# rpi_gnss_board.net
KiCad netlist of a schematic drawn in EAGLE
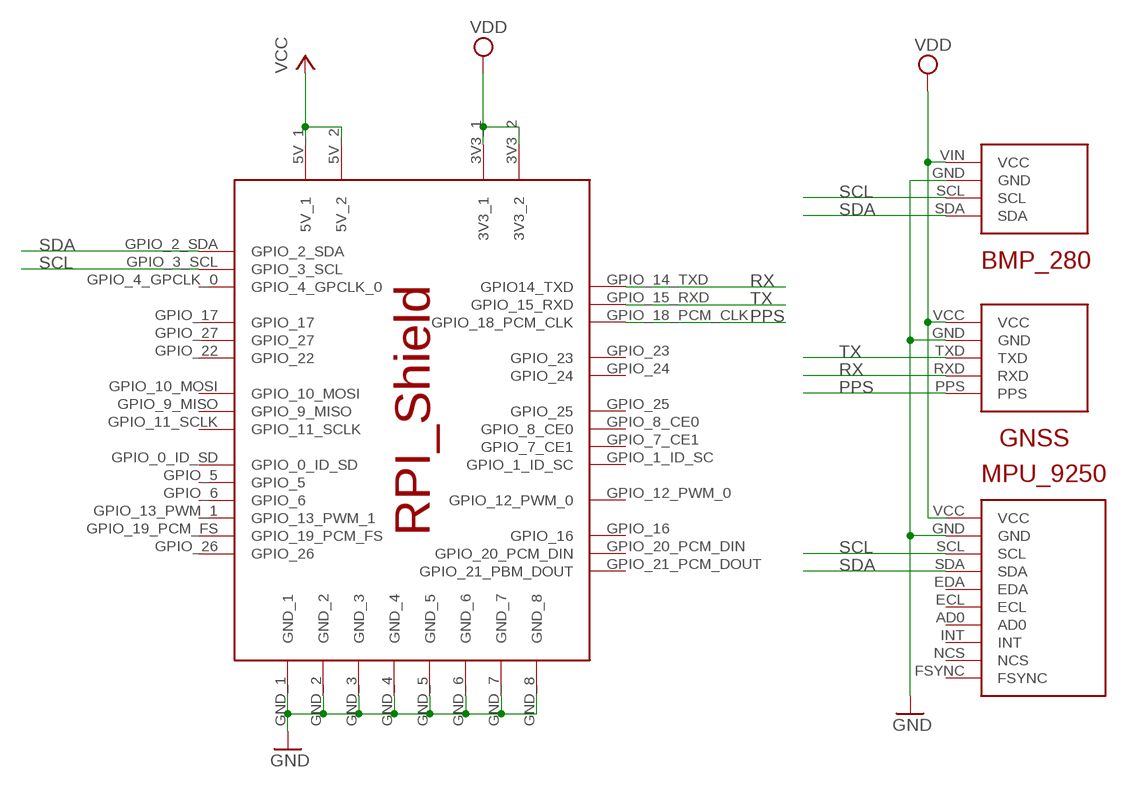
[diagram p0: schematic, sheet 1]

(export (version "E")
  (design (tool "Eeschema 10.0.6"))
  (components
    (comp (ref "U$1")
      (value "RPI_SHIELD")
      (footprint "eagle-import:RPI_SHIELD")
      (libsource (lib "eagle-import") (part "RPI_SHIELD"))
    )
    (comp (ref "U$2")
      (value "BMP_280")
      (footprint "eagle-import:BMP_280")
      (libsource (lib "eagle-import") (part "BMP_280"))
    )
    (comp (ref "U$3")
      (value "GNSS_MODULE_UBLOX")
      (footprint "eagle-import:GNSS_MODULE_UBLOX")
      (libsource (lib "eagle-import") (part "GNSS_MODULE_UBLOX"))
    )
    (comp (ref "U$4")
      (value "MPU_9250")
      (footprint "eagle-import:MPU_9250")
      (libsource (lib "eagle-import") (part "MPU_9250"))
    )
  )
  (nets
    (net (code "1") (name "/PPS") (class "Default")
      (node (ref "U$1") (pin "GPIO_18_PCM_CLK") (pinfunction "GPIO_18_PCM_CLK_GPIO_18_PCM_CLK") (pintype "bidirectional"))
      (node (ref "U$3") (pin "PPS") (pinfunction "PPS_PPS") (pintype "bidirectional"))
    )
    (net (code "2") (name "/RX") (class "Default")
      (node (ref "U$1") (pin "GPIO_14_TXD") (pinfunction "GPIO14_TXD_GPIO_14_TXD") (pintype "bidirectional"))
      (node (ref "U$3") (pin "RXD") (pinfunction "RXD_RXD") (pintype "bidirectional"))
    )
    (net (code "3") (name "/SCL") (class "Default")
      (node (ref "U$1") (pin "GPIO_3_SCL") (pinfunction "GPIO_3_SCL_GPIO_3_SCL") (pintype "bidirectional"))
      (node (ref "U$2") (pin "SCL") (pinfunction "SCL_SCL") (pintype "bidirectional"))
      (node (ref "U$4") (pin "SCL") (pinfunction "SCL_SCL") (pintype "bidirectional"))
    )
    (net (code "4") (name "/SDA") (class "Default")
      (node (ref "U$1") (pin "GPIO_2_SDA") (pinfunction "GPIO_2_SDA_GPIO_2_SDA") (pintype "bidirectional"))
      (node (ref "U$2") (pin "SDA") (pinfunction "SDA_SDA") (pintype "bidirectional"))
      (node (ref "U$4") (pin "SDA") (pinfunction "SDA_SDA") (pintype "bidirectional"))
    )
    (net (code "5") (name "/TX") (class "Default")
      (node (ref "U$1") (pin "GPIO_15_RXD") (pinfunction "GPIO_15_RXD_GPIO_15_RXD") (pintype "bidirectional"))
      (node (ref "U$3") (pin "TXD") (pinfunction "TXD_TXD") (pintype "bidirectional"))
    )
    (net (code "6") (name "GND") (class "Default")
      (node (ref "U$1") (pin "GND_1") (pinfunction "GND_1_GND_1") (pintype "bidirectional"))
      (node (ref "U$1") (pin "GND_2") (pinfunction "GND_2_GND_2") (pintype "bidirectional"))
      (node (ref "U$1") (pin "GND_3") (pinfunction "GND_3_GND_3") (pintype "bidirectional"))
      (node (ref "U$1") (pin "GND_4") (pinfunction "GND_4_GND_4") (pintype "bidirectional"))
      (node (ref "U$1") (pin "GND_5") (pinfunction "GND_5_GND_5") (pintype "bidirectional"))
      (node (ref "U$1") (pin "GND_6") (pinfunction "GND_6_GND_6") (pintype "bidirectional"))
      (node (ref "U$1") (pin "GND_7") (pinfunction "GND_7_GND_7") (pintype "bidirectional"))
      (node (ref "U$1") (pin "GND_8") (pinfunction "GND_8_GND_8") (pintype "bidirectional"))
      (node (ref "U$2") (pin "GND") (pinfunction "GND_GND") (pintype "bidirectional"))
      (node (ref "U$3") (pin "GND") (pinfunction "GND_GND") (pintype "bidirectional"))
      (node (ref "U$4") (pin "GND") (pinfunction "GND_GND") (pintype "bidirectional"))
    )
    (net (code "7") (name "VCC") (class "Default")
      (node (ref "U$1") (pin "5V_1") (pinfunction "5V_1_5V_1") (pintype "bidirectional"))
      (node (ref "U$1") (pin "5V_2") (pinfunction "5V_2_5V_2") (pintype "bidirectional"))
    )
    (net (code "8") (name "VDD") (class "Default")
      (node (ref "U$1") (pin "3V3_1") (pinfunction "3V3_1_3V3_1") (pintype "bidirectional"))
      (node (ref "U$1") (pin "3V3_2") (pinfunction "3V3_2_3V3_2") (pintype "bidirectional"))
      (node (ref "U$2") (pin "VIN") (pinfunction "VCC_VIN") (pintype "bidirectional"))
      (node (ref "U$3") (pin "VCC") (pinfunction "VCC_VCC") (pintype "bidirectional"))
      (node (ref "U$4") (pin "VCC") (pinfunction "VCC_VCC") (pintype "bidirectional"))
    )
    (net (code "9") (name "unconnected-(U$1-GPIO_21_PBM_DOUT-PadGPIO_21_PCM_DOUT)") (class "Default")
      (node (ref "U$1") (pin "GPIO_21_PCM_DOUT") (pinfunction "GPIO_21_PBM_DOUT_GPIO_21_PCM_DOUT") (pintype "bidirectional"))
    )
    (net (code "10") (name "unconnected-(U$1-PadGPIO_0_ID_SD)") (class "Default")
      (node (ref "U$1") (pin "GPIO_0_ID_SD") (pinfunction "GPIO_0_ID_SD_GPIO_0_ID_SD") (pintype "bidirectional"))
    )
    (net (code "11") (name "unconnected-(U$1-PadGPIO_1_ID_SC)") (class "Default")
      (node (ref "U$1") (pin "GPIO_1_ID_SC") (pinfunction "GPIO_1_ID_SC_GPIO_1_ID_SC") (pintype "bidirectional"))
    )
    (net (code "12") (name "unconnected-(U$1-PadGPIO_4_GPCLK_0)") (class "Default")
      (node (ref "U$1") (pin "GPIO_4_GPCLK_0") (pinfunction "GPIO_4_GPCLK_0_GPIO_4_GPCLK_0") (pintype "bidirectional"))
    )
    (net (code "13") (name "unconnected-(U$1-PadGPIO_5)") (class "Default")
      (node (ref "U$1") (pin "GPIO_5") (pinfunction "GPIO_5_GPIO_5") (pintype "bidirectional"))
    )
    (net (code "14") (name "unconnected-(U$1-PadGPIO_6)") (class "Default")
      (node (ref "U$1") (pin "GPIO_6") (pinfunction "GPIO_6_GPIO_6") (pintype "bidirectional"))
    )
    (net (code "15") (name "unconnected-(U$1-PadGPIO_7_CE1)") (class "Default")
      (node (ref "U$1") (pin "GPIO_7_CE1") (pinfunction "GPIO_7_CE1_GPIO_7_CE1") (pintype "bidirectional"))
    )
    (net (code "16") (name "unconnected-(U$1-PadGPIO_8_CE0)") (class "Default")
      (node (ref "U$1") (pin "GPIO_8_CE0") (pinfunction "GPIO_8_CE0_GPIO_8_CE0") (pintype "bidirectional"))
    )
    (net (code "17") (name "unconnected-(U$1-PadGPIO_9_MISO)") (class "Default")
      (node (ref "U$1") (pin "GPIO_9_MISO") (pinfunction "GPIO_9_MISO_GPIO_9_MISO") (pintype "bidirectional"))
    )
    (net (code "18") (name "unconnected-(U$1-PadGPIO_10_MOSI)") (class "Default")
      (node (ref "U$1") (pin "GPIO_10_MOSI") (pinfunction "GPIO_10_MOSI_GPIO_10_MOSI") (pintype "bidirectional"))
    )
    (net (code "19") (name "unconnected-(U$1-PadGPIO_11_SCLK)") (class "Default")
      (node (ref "U$1") (pin "GPIO_11_SCLK") (pinfunction "GPIO_11_SCLK_GPIO_11_SCLK") (pintype "bidirectional"))
    )
    (net (code "20") (name "unconnected-(U$1-PadGPIO_12_PWM_0)") (class "Default")
      (node (ref "U$1") (pin "GPIO_12_PWM_0") (pinfunction "GPIO_12_PWM_0_GPIO_12_PWM_0") (pintype "bidirectional"))
    )
    (net (code "21") (name "unconnected-(U$1-PadGPIO_13_PWM_1)") (class "Default")
      (node (ref "U$1") (pin "GPIO_13_PWM_1") (pinfunction "GPIO_13_PWM_1_GPIO_13_PWM_1") (pintype "bidirectional"))
    )
    (net (code "22") (name "unconnected-(U$1-PadGPIO_16)") (class "Default")
      (node (ref "U$1") (pin "GPIO_16") (pinfunction "GPIO_16_GPIO_16") (pintype "bidirectional"))
    )
    (net (code "23") (name "unconnected-(U$1-PadGPIO_17)") (class "Default")
      (node (ref "U$1") (pin "GPIO_17") (pinfunction "GPIO_17_GPIO_17") (pintype "bidirectional"))
    )
    (net (code "24") (name "unconnected-(U$1-PadGPIO_19_PCM_FS)") (class "Default")
      (node (ref "U$1") (pin "GPIO_19_PCM_FS") (pinfunction "GPIO_19_PCM_FS_GPIO_19_PCM_FS") (pintype "bidirectional"))
    )
    (net (code "25") (name "unconnected-(U$1-PadGPIO_20_PCM_DIN)") (class "Default")
      (node (ref "U$1") (pin "GPIO_20_PCM_DIN") (pinfunction "GPIO_20_PCM_DIN_GPIO_20_PCM_DIN") (pintype "bidirectional"))
    )
    (net (code "26") (name "unconnected-(U$1-PadGPIO_22)") (class "Default")
      (node (ref "U$1") (pin "GPIO_22") (pinfunction "GPIO_22_GPIO_22") (pintype "bidirectional"))
    )
    (net (code "27") (name "unconnected-(U$1-PadGPIO_23)") (class "Default")
      (node (ref "U$1") (pin "GPIO_23") (pinfunction "GPIO_23_GPIO_23") (pintype "bidirectional"))
    )
    (net (code "28") (name "unconnected-(U$1-PadGPIO_24)") (class "Default")
      (node (ref "U$1") (pin "GPIO_24") (pinfunction "GPIO_24_GPIO_24") (pintype "bidirectional"))
    )
    (net (code "29") (name "unconnected-(U$1-PadGPIO_25)") (class "Default")
      (node (ref "U$1") (pin "GPIO_25") (pinfunction "GPIO_25_GPIO_25") (pintype "bidirectional"))
    )
    (net (code "30") (name "unconnected-(U$1-PadGPIO_26)") (class "Default")
      (node (ref "U$1") (pin "GPIO_26") (pinfunction "GPIO_26_GPIO_26") (pintype "bidirectional"))
    )
    (net (code "31") (name "unconnected-(U$1-PadGPIO_27)") (class "Default")
      (node (ref "U$1") (pin "GPIO_27") (pinfunction "GPIO_27_GPIO_27") (pintype "bidirectional"))
    )
    (net (code "32") (name "unconnected-(U$4-PadAD0)") (class "Default")
      (node (ref "U$4") (pin "AD0") (pinfunction "AD0_AD0") (pintype "bidirectional"))
    )
    (net (code "33") (name "unconnected-(U$4-PadECL)") (class "Default")
      (node (ref "U$4") (pin "ECL") (pinfunction "ECL_ECL") (pintype "bidirectional"))
    )
    (net (code "34") (name "unconnected-(U$4-PadEDA)") (class "Default")
      (node (ref "U$4") (pin "EDA") (pinfunction "EDA_EDA") (pintype "bidirectional"))
    )
    (net (code "35") (name "unconnected-(U$4-PadFSYNC)") (class "Default")
      (node (ref "U$4") (pin "FSYNC") (pinfunction "FSYNC_FSYNC") (pintype "bidirectional"))
    )
    (net (code "36") (name "unconnected-(U$4-PadINT)") (class "Default")
      (node (ref "U$4") (pin "INT") (pinfunction "INT_INT") (pintype "bidirectional"))
    )
    (net (code "37") (name "unconnected-(U$4-PadNCS)") (class "Default")
      (node (ref "U$4") (pin "NCS") (pinfunction "NCS_NCS") (pintype "bidirectional"))
    )
  )
)
